# dil_oscillator.net
KiCad netlist of a schematic drawn in EAGLE
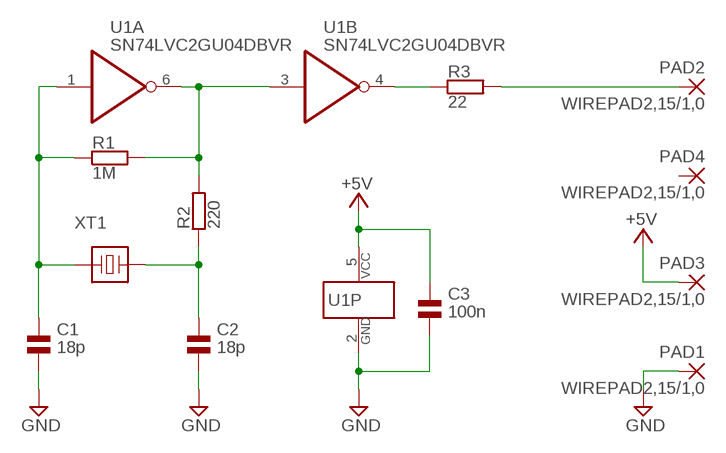
[diagram p0: schematic, sheet 1]

(export (version "E")
  (design (tool "Eeschema 10.0.6"))
  (components
    (comp (ref "C1")
      (value "18p")
      (footprint "eagle-import:0603")
      (libsource (lib "eagle-import") (part "CAP_NPOL0603-"))
    )
    (comp (ref "C2")
      (value "18p")
      (footprint "eagle-import:0603")
      (libsource (lib "eagle-import") (part "CAP_NPOL0603-"))
    )
    (comp (ref "C3")
      (value "100n")
      (footprint "eagle-import:0603")
      (libsource (lib "eagle-import") (part "CAP_NPOL0603-"))
    )
    (comp (ref "PAD1")
      (value "WIREPAD2,15/1,0")
      (footprint "eagle-import:2,15_1,0")
      (libsource (lib "eagle-import") (part "WIREPAD2,15/1,0"))
    )
    (comp (ref "PAD2")
      (value "WIREPAD2,15/1,0")
      (footprint "eagle-import:2,15_1,0")
      (libsource (lib "eagle-import") (part "WIREPAD2,15/1,0"))
    )
    (comp (ref "PAD3")
      (value "WIREPAD2,15/1,0")
      (footprint "eagle-import:2,15_1,0")
      (libsource (lib "eagle-import") (part "WIREPAD2,15/1,0"))
    )
    (comp (ref "PAD4")
      (value "WIREPAD2,15/1,0")
      (footprint "eagle-import:2,15_1,0")
      (libsource (lib "eagle-import") (part "WIREPAD2,15/1,0"))
    )
    (comp (ref "R1")
      (value "1M")
      (footprint "eagle-import:0603")
      (libsource (lib "eagle-import") (part "RESSMD_0603-"))
    )
    (comp (ref "R2")
      (value "220")
      (footprint "eagle-import:0603")
      (libsource (lib "eagle-import") (part "RESSMD_0603-"))
    )
    (comp (ref "R3")
      (value "22")
      (footprint "eagle-import:0603")
      (libsource (lib "eagle-import") (part "RESSMD_0603-"))
    )
    (comp (ref "U1")
      (value "SN74LVC2GU04DBVR")
      (footprint "eagle-import:SOT457")
      (libsource (lib "eagle-import") (part "742GU04GVHC"))
    )
    (comp (ref "XT1")
      (value "XTAL_3225")
      (footprint "eagle-import:3225_4PAD")
      (libsource (lib "eagle-import") (part "XTAL_3225"))
    )
  )
  (nets
    (net (code "1") (name "+5V") (class "Default")
      (node (ref "C3") (pin "1") (pinfunction "1_1") (pintype "passive"))
      (node (ref "PAD3") (pin "1") (pinfunction "P_1") (pintype "passive"))
      (node (ref "U1") (pin "5") (pinfunction "VCC_5") (pintype "power_in"))
    )
    (net (code "2") (name "GND") (class "Default")
      (node (ref "C1") (pin "2") (pinfunction "2_2") (pintype "passive"))
      (node (ref "C2") (pin "2") (pinfunction "2_2") (pintype "passive"))
      (node (ref "C3") (pin "2") (pinfunction "2_2") (pintype "passive"))
      (node (ref "PAD1") (pin "1") (pinfunction "P_1") (pintype "passive"))
      (node (ref "U1") (pin "2") (pinfunction "GND_2") (pintype "power_in"))
    )
    (net (code "3") (name "Net-(PAD2-P)") (class "Default")
      (node (ref "PAD2") (pin "1") (pinfunction "P_1") (pintype "passive"))
      (node (ref "R3") (pin "2") (pinfunction "2_2") (pintype "passive"))
    )
    (net (code "4") (name "Net-(U1A-I)") (class "Default")
      (node (ref "C1") (pin "1") (pinfunction "1_1") (pintype "passive"))
      (node (ref "R1") (pin "1") (pinfunction "1_1") (pintype "passive"))
      (node (ref "U1") (pin "1") (pinfunction "I_1") (pintype "input"))
      (node (ref "XT1") (pin "1") (pinfunction "1_1") (pintype "passive"))
    )
    (net (code "5") (name "Net-(U1A-O)") (class "Default")
      (node (ref "R1") (pin "2") (pinfunction "2_2") (pintype "passive"))
      (node (ref "R2") (pin "2") (pinfunction "2_2") (pintype "passive"))
      (node (ref "U1") (pin "3") (pinfunction "I_3") (pintype "input"))
      (node (ref "U1") (pin "6") (pinfunction "O_6") (pintype "output"))
    )
    (net (code "6") (name "Net-(U1B-O)") (class "Default")
      (node (ref "R3") (pin "1") (pinfunction "1_1") (pintype "passive"))
      (node (ref "U1") (pin "4") (pinfunction "O_4") (pintype "output"))
    )
    (net (code "7") (name "Net-(XT1-2)") (class "Default")
      (node (ref "C2") (pin "1") (pinfunction "1_1") (pintype "passive"))
      (node (ref "R2") (pin "1") (pinfunction "1_1") (pintype "passive"))
      (node (ref "XT1") (pin "3") (pinfunction "2_3") (pintype "passive"))
    )
    (net (code "8") (name "unconnected-(PAD4-P-Pad1)") (class "Default")
      (node (ref "PAD4") (pin "1") (pinfunction "P_1") (pintype "passive"))
    )
  )
)
